# MAIN.net
KiCad netlist of a schematic drawn in Altium Designer
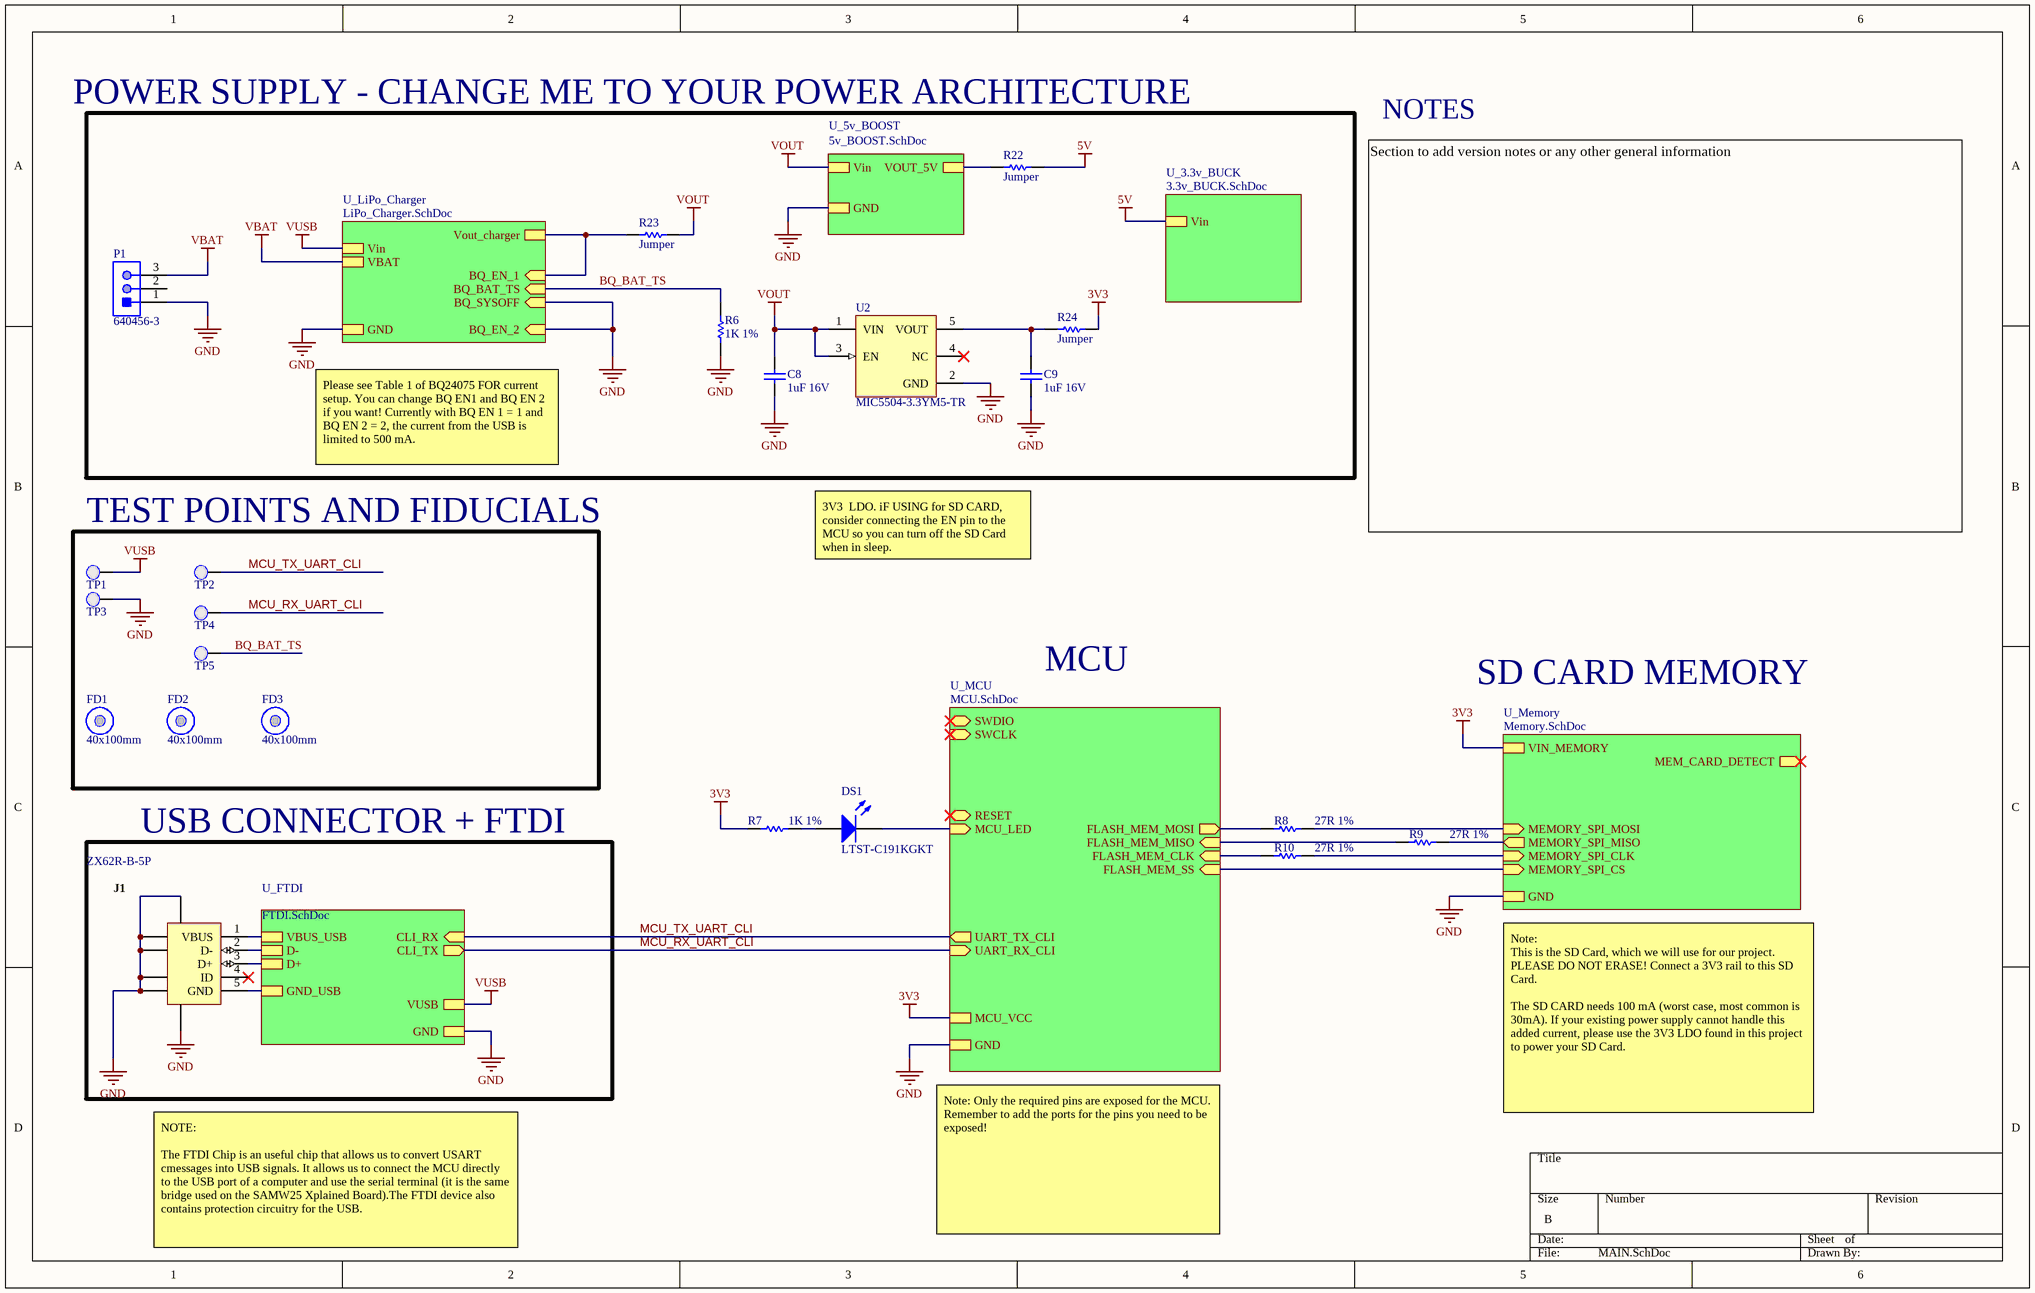
[diagram p0: MAIN.SchDoc]

(export (version "E")
  (design (tool "Eeschema 10.0.6"))
  (components
    (comp (ref "C8")
      (value "1uF 16V")
      (footprint "CAPC0603(1608)100_N")
      (description "CAP 1uF 16V ±5% 0603 (1608 Metric) Thickness 1mm SMD")
      (fields (field (name "TOLERANCE") "Â±5%"))
      (libsource (lib "Altium Content Vault") (part "CAP"))
    )
    (comp (ref "C9")
      (value "1uF 16V")
      (footprint "CAPC0603(1608)100_N")
      (description "CAP 1uF 16V ±5% 0603 (1608 Metric) Thickness 1mm SMD")
      (fields (field (name "TOLERANCE") "Â±5%"))
      (libsource (lib "Altium Content Vault") (part "CAP"))
    )
    (comp (ref "DS1")
      (value "LTST-C191KGKT")
      (footprint "LITE-ON-LTST-C191KRKT-2_V")
      (description "Chip LED, Green, 574 nm, 40 pF, -55 to 85 degC, 2-Pin SMD, RoHS, Tape and Reel")
      (fields (field (name "MANUFACTURER") "Lite-On"))
      (libsource (lib "Altium Content Vault") (part "LED-AK-2"))
    )
    (comp (ref "FD1")
      (value "40x100mm")
      (footprint "Fiducial_FT")
      (description "Fiducial 40x100mm")
      (libsource (lib "Components - 01.02.21 - 21.11") (part "CMP-00174-A.4"))
    )
    (comp (ref "FD2")
      (value "40x100mm")
      (footprint "Fiducial_FT")
      (description "Fiducial 40x100mm")
      (libsource (lib "Components - 01.02.21 - 21.11") (part "CMP-00174-A.4"))
    )
    (comp (ref "FD3")
      (value "40x100mm")
      (footprint "Fiducial_FT")
      (description "Fiducial 40x100mm")
      (libsource (lib "Components - 01.02.21 - 21.11") (part "CMP-00174-A.4"))
    )
    (comp (ref "J1")
      (value "ZX62R-B-5P")
      (footprint "HIRO-ZX62R-B-5P_V")
      (description "Connector; USBMicro-B,Reverse type, SMT; 5 Position; Right Angle")
      (libsource (lib "Altium Content Vault") (part "HIRO-ZX62R-B-5P-5"))
    )
    (comp (ref "P1")
      (value "640456-3")
      (footprint "TECO-640456-3")
      (description "Male Header, Pitch 2.54 mm, 1 x 3 Position, Height 10.03 mm, Tail Length 3.56 mm, -55 to 105 degC")
      (fields (field (name "MANUFACTURER") "TE Connectivity"))
      (libsource (lib "Altium Content Vault") (part "CN-1P-M-R3"))
    )
    (comp (ref "R6")
      (value "1K 1%")
      (footprint "RESC0603(1608)_N")
      (description "1K 0.1W 1% 0603 (1608 Metric)  SMD")
      (fields (field (name "TOLERANCE") "1 %") (field (name "POWER") "0.1 W"))
      (libsource (lib "Altium Content Vault") (part "RES"))
    )
    (comp (ref "R7")
      (value "1K 1%")
      (footprint "RESC0603(1608)_N")
      (description "1K 0.1W 1% 0603 (1608 Metric)  SMD")
      (fields (field (name "TOLERANCE") "1 %") (field (name "POWER") "0.1 W"))
      (libsource (lib "Altium Content Vault") (part "RES"))
    )
    (comp (ref "R8")
      (value "27R 1%")
      (footprint "RESC0603(1608)_N")
      (description "27R 0.1W 1% 0603 (1608 Metric)  SMD")
      (fields (field (name "TOLERANCE") "1 %") (field (name "POWER") "0.1 W"))
      (libsource (lib "Altium Content Vault") (part "RES"))
    )
    (comp (ref "R9")
      (value "27R 1%")
      (footprint "RESC0603(1608)_N")
      (description "27R 0.1W 1% 0603 (1608 Metric)  SMD")
      (fields (field (name "TOLERANCE") "1 %") (field (name "POWER") "0.1 W"))
      (libsource (lib "Altium Content Vault") (part "RES"))
    )
    (comp (ref "R10")
      (value "27R 1%")
      (footprint "RESC0603(1608)_N")
      (description "27R 0.1W 1% 0603 (1608 Metric)  SMD")
      (fields (field (name "TOLERANCE") "1 %") (field (name "POWER") "0.1 W"))
      (libsource (lib "Altium Content Vault") (part "RES"))
    )
    (comp (ref "R22")
      (value "Jumper")
      (footprint "RESC0805(2012)_N")
      (description "Jumper 0805 (2012 Metric)")
      (fields (field (name "TOLERANCE") "None"))
      (libsource (lib "Altium Content Vault") (part "RES"))
    )
    (comp (ref "R23")
      (value "Jumper")
      (footprint "RESC0805(2012)_N")
      (description "Jumper 0805 (2012 Metric)")
      (fields (field (name "TOLERANCE") "None"))
      (libsource (lib "Altium Content Vault") (part "RES"))
    )
    (comp (ref "R24")
      (value "Jumper")
      (footprint "RESC0805(2012)_N")
      (description "Jumper 0805 (2012 Metric)")
      (fields (field (name "TOLERANCE") "None"))
      (libsource (lib "Altium Content Vault") (part "RES"))
    )
    (comp (ref "TP1")
      (value "0.1\" Pad")
      (footprint "PCBComponent")
      (libsource (lib "Components - 12.02.20 - 18.05") (part "0.1{dblquote} Pad-A.4"))
    )
    (comp (ref "TP2")
      (value "0.1\" Pad")
      (footprint "PCBComponent")
      (libsource (lib "Components - 12.02.20 - 18.05") (part "0.1{dblquote} Pad-A.4"))
    )
    (comp (ref "TP3")
      (value "0.1\" Pad")
      (footprint "PCBComponent")
      (libsource (lib "Components - 12.02.20 - 18.05") (part "0.1{dblquote} Pad-A.4"))
    )
    (comp (ref "TP4")
      (value "0.1\" Pad")
      (footprint "PCBComponent")
      (libsource (lib "Components - 12.02.20 - 18.05") (part "0.1{dblquote} Pad-A.4"))
    )
    (comp (ref "TP5")
      (value "0.1\" Pad")
      (footprint "PCBComponent")
      (libsource (lib "Components - 12.02.20 - 18.05") (part "0.1{dblquote} Pad-A.4"))
    )
    (comp (ref "U2")
      (value "MIC5504-3.3YM5-TR")
      (footprint "MCHP-SOT-23-M5_V")
      (fields (field (name "MANUFACTURER") "Microchip"))
      (libsource (lib "Altium Content Vault") (part "MCHP-MIC5504-SOT-23-M5"))
    )
  )
  (nets
    (net (code "1") (name "/BQ_BAT_TS") (class "Default")
      (node (ref "R6") (pin "1") (pinfunction "1_1") (pintype "passive"))
      (node (ref "TP5") (pin "1") (pinfunction "PAD_1") (pintype "passive"))
    )
    (net (code "2") (name "/BQ_EN_1") (class "Default")
      (node (ref "R23") (pin "1") (pinfunction "1_1") (pintype "passive"))
    )
    (net (code "3") (name "/D+") (class "Default")
      (node (ref "J1") (pin "3") (pinfunction "D+_3") (pintype "bidirectional"))
    )
    (net (code "4") (name "/D-") (class "Default")
      (node (ref "J1") (pin "2") (pinfunction "D-_2") (pintype "bidirectional"))
    )
    (net (code "5") (name "/FLASH_MEM_CLK") (class "Default")
      (node (ref "R10") (pin "1") (pinfunction "1_1") (pintype "passive"))
    )
    (net (code "6") (name "/FLASH_MEM_MISO") (class "Default")
      (node (ref "R9") (pin "1") (pinfunction "1_1") (pintype "passive"))
    )
    (net (code "7") (name "/FLASH_MEM_MOSI") (class "Default")
      (node (ref "R8") (pin "1") (pinfunction "1_1") (pintype "passive"))
    )
    (net (code "9") (name "/GND_USB") (class "Default")
      (node (ref "J1") (pin "5") (pinfunction "GND_5") (pintype "power_in"))
    )
    (net (code "10") (name "/MCU_LED") (class "Default")
      (node (ref "DS1") (pin "2") (pinfunction "K_2") (pintype "passive"))
    )
    (net (code "11") (name "/MCU_RX_UART_CLI") (class "Default")
      (node (ref "TP4") (pin "1") (pinfunction "PAD_1") (pintype "passive"))
    )
    (net (code "12") (name "/MCU_TX_UART_CLI") (class "Default")
      (node (ref "TP2") (pin "1") (pinfunction "PAD_1") (pintype "passive"))
    )
    (net (code "13") (name "/MEMORY_SPI_CLK") (class "Default")
      (node (ref "R10") (pin "2") (pinfunction "2_2") (pintype "passive"))
    )
    (net (code "14") (name "/MEMORY_SPI_MISO") (class "Default")
      (node (ref "R9") (pin "2") (pinfunction "2_2") (pintype "passive"))
    )
    (net (code "15") (name "/MEMORY_SPI_MOSI") (class "Default")
      (node (ref "R8") (pin "2") (pinfunction "2_2") (pintype "passive"))
    )
    (net (code "20") (name "/VBUS_USB") (class "Default")
      (node (ref "J1") (pin "1") (pinfunction "VBUS_1") (pintype "power_in"))
    )
    (net (code "21") (name "/VOUT_5V") (class "Default")
      (node (ref "R22") (pin "1") (pinfunction "1_1") (pintype "passive"))
    )
    (net (code "22") (name "3V3") (class "Default")
      (node (ref "R24") (pin "2") (pinfunction "2_2") (pintype "passive"))
      (node (ref "R7") (pin "1") (pinfunction "1_1") (pintype "passive"))
    )
    (net (code "23") (name "5V") (class "Default")
      (node (ref "R22") (pin "2") (pinfunction "2_2") (pintype "passive"))
    )
    (net (code "24") (name "GND") (class "Default")
      (node (ref "C8") (pin "1") (pinfunction "1_1") (pintype "passive"))
      (node (ref "C9") (pin "1") (pinfunction "1_1") (pintype "passive"))
      (node (ref "J1") (pin "10") (pinfunction "SHLD_10") (pintype "passive"))
      (node (ref "J1") (pin "11") (pinfunction "SHLD_11") (pintype "passive"))
      (node (ref "J1") (pin "6") (pinfunction "SHLD_6") (pintype "passive"))
      (node (ref "J1") (pin "7") (pinfunction "SHLD_7") (pintype "passive"))
      (node (ref "J1") (pin "8") (pinfunction "SHLD_8") (pintype "passive"))
      (node (ref "J1") (pin "9") (pinfunction "SHLD_9") (pintype "passive"))
      (node (ref "P1") (pin "1") (pinfunction "1_1") (pintype "passive"))
      (node (ref "R6") (pin "2") (pinfunction "2_2") (pintype "passive"))
      (node (ref "TP3") (pin "1") (pinfunction "PAD_1") (pintype "passive"))
      (node (ref "U2") (pin "2") (pinfunction "GND_2") (pintype "power_in"))
    )
    (net (code "25") (name "Net-(DS1-A)") (class "Default")
      (node (ref "DS1") (pin "1") (pinfunction "A_1") (pintype "passive"))
      (node (ref "R7") (pin "2") (pinfunction "2_2") (pintype "passive"))
    )
    (net (code "26") (name "Net-(U2-VOUT)") (class "Default")
      (node (ref "C9") (pin "2") (pinfunction "2_2") (pintype "passive"))
      (node (ref "R24") (pin "1") (pinfunction "1_1") (pintype "passive"))
      (node (ref "U2") (pin "5") (pinfunction "VOUT_5") (pintype "power_in"))
    )
    (net (code "27") (name "VBAT") (class "Default")
      (node (ref "P1") (pin "3") (pinfunction "3_3") (pintype "passive"))
    )
    (net (code "28") (name "VOUT") (class "Default")
      (node (ref "C8") (pin "2") (pinfunction "2_2") (pintype "passive"))
      (node (ref "R23") (pin "2") (pinfunction "2_2") (pintype "passive"))
      (node (ref "U2") (pin "1") (pinfunction "VIN_1") (pintype "power_in"))
      (node (ref "U2") (pin "3") (pinfunction "EN_3") (pintype "input"))
    )
    (net (code "29") (name "VUSB") (class "Default")
      (node (ref "TP1") (pin "1") (pinfunction "PAD_1") (pintype "passive"))
    )
    (net (code "30") (name "unconnected-(J1-ID-Pad4)") (class "Default")
      (node (ref "J1") (pin "4") (pinfunction "ID_4") (pintype "passive+no_connect"))
    )
    (net (code "31") (name "unconnected-(P1-Pad2)") (class "Default")
      (node (ref "P1") (pin "2") (pinfunction "2_2") (pintype "passive"))
    )
    (net (code "32") (name "unconnected-(U2-NC-Pad4)") (class "Default")
      (node (ref "U2") (pin "4") (pinfunction "NC_4") (pintype "passive+no_connect"))
    )
  )
)
